# CW521_BallisticGel_Main.net
KiCad netlist of a schematic drawn in Altium Designer
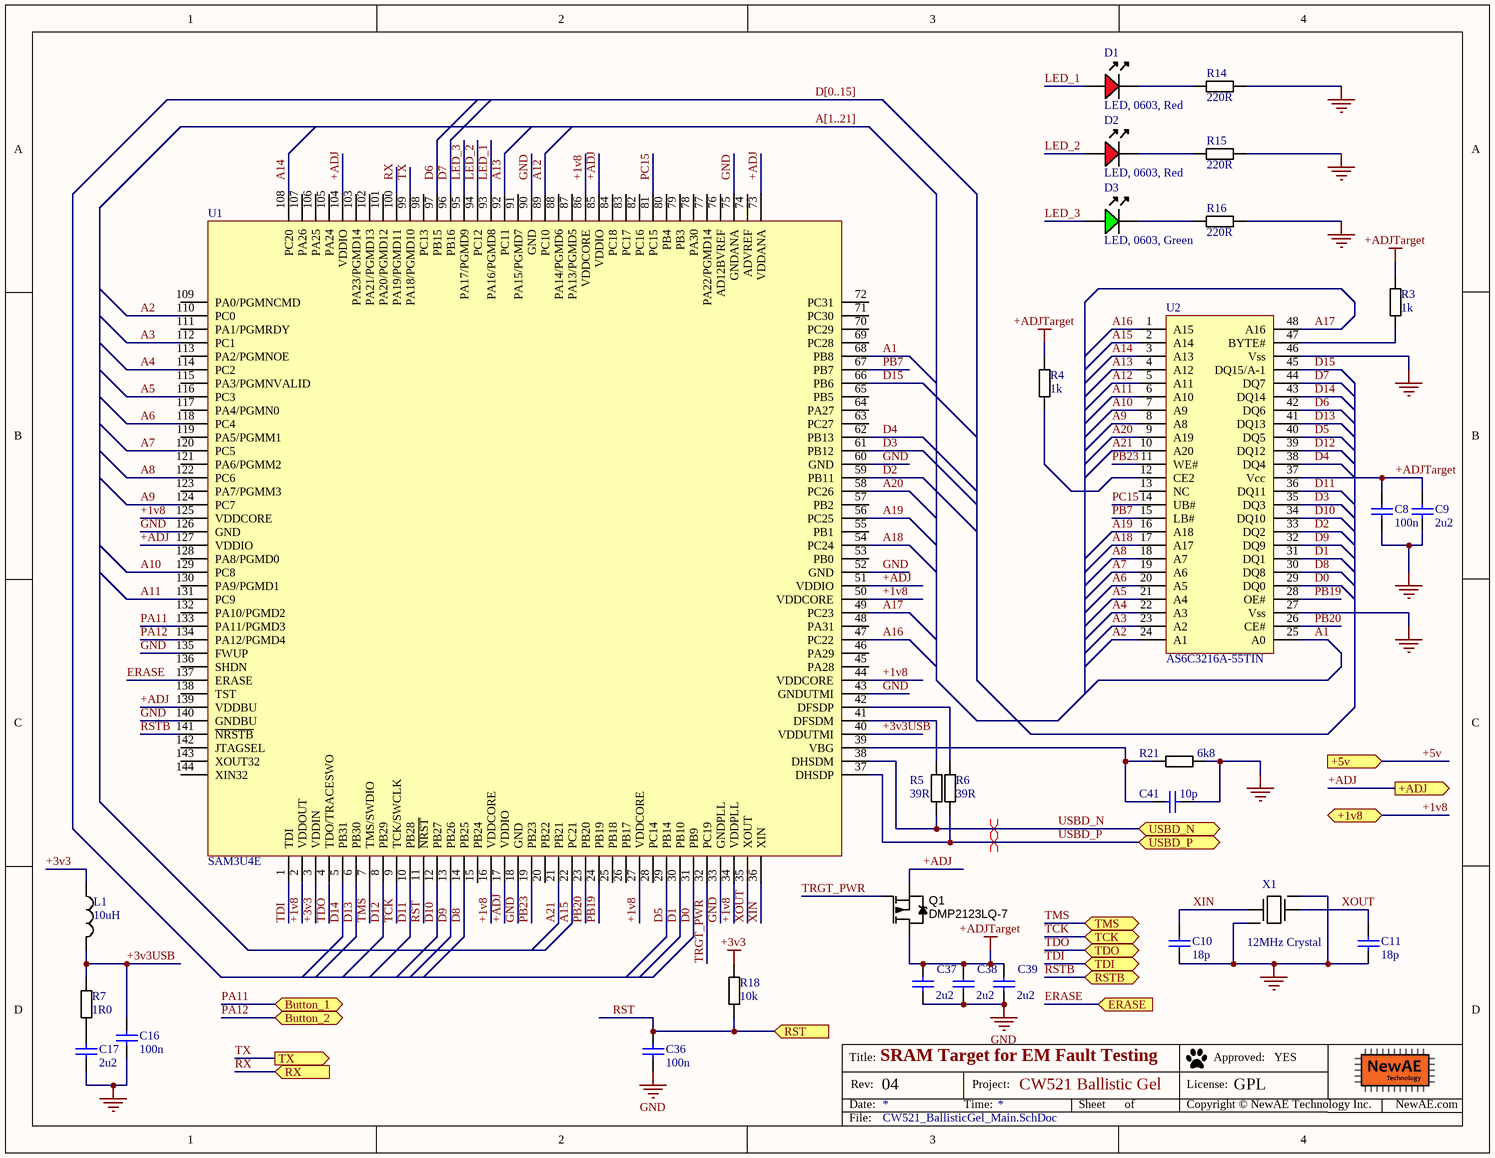
[diagram p0: CW521_BallisticGel_Main.SchDoc]

(export (version "E")
  (design (tool "Eeschema 10.0.6"))
  (components
    (comp (ref "C8")
      (value "100n")
      (footprint "CAPC0603_M")
      (description "100n, 0603")
      (fields (field (name "PART NUMBER") "CCHIP-100n-0603"))
      (libsource (lib "NewAE_AltiumLib") (part "CAP"))
    )
    (comp (ref "C9")
      (value "2u2")
      (footprint "CAPC0603_M")
      (description "2u2, 0603")
      (fields (field (name "PART NUMBER") "CCHIP-2u2-0603"))
      (libsource (lib "NewAE_AltiumLib") (part "CAP"))
    )
    (comp (ref "C10")
      (value "18p")
      (footprint "CAPC0402_M")
      (description "18p, 0402")
      (fields (field (name "PART NUMBER") "CCHIP-18p-0402"))
      (libsource (lib "NewAE_AltiumLib") (part "CAP"))
    )
    (comp (ref "C11")
      (value "18p")
      (footprint "CAPC0402_M")
      (description "18p, 0402")
      (fields (field (name "PART NUMBER") "CCHIP-18p-0402"))
      (libsource (lib "NewAE_AltiumLib") (part "CAP"))
    )
    (comp (ref "C16")
      (value "100n")
      (footprint "CAPC0603_M")
      (description "100n, 0603")
      (fields (field (name "PART NUMBER") "CCHIP-100n-0603"))
      (libsource (lib "NewAE_AltiumLib") (part "CAP"))
    )
    (comp (ref "C17")
      (value "2u2")
      (footprint "CAPC0603_M")
      (description "2u2, 0603")
      (fields (field (name "PART NUMBER") "CCHIP-2u2-0603"))
      (libsource (lib "NewAE_AltiumLib") (part "CAP"))
    )
    (comp (ref "C36")
      (value "100n")
      (footprint "CAPC0603_M")
      (description "100n, 0603")
      (fields (field (name "PART NUMBER") "CCHIP-100n-0603"))
      (libsource (lib "NewAE_AltiumLib") (part "CAP"))
    )
    (comp (ref "C37")
      (value "2u2")
      (footprint "CAPC0603_M")
      (description "2u2, 0603")
      (fields (field (name "PART NUMBER") "CCHIP-2u2-0603"))
      (libsource (lib "NewAE_AltiumLib") (part "CAP"))
    )
    (comp (ref "C38")
      (value "2u2")
      (footprint "CAPC0603_M")
      (description "2u2, 0603")
      (fields (field (name "PART NUMBER") "CCHIP-2u2-0603"))
      (libsource (lib "NewAE_AltiumLib") (part "CAP"))
    )
    (comp (ref "C39")
      (value "2u2")
      (footprint "CAPC0603_M")
      (description "2u2, 0603")
      (fields (field (name "PART NUMBER") "CCHIP-2u2-0603"))
      (libsource (lib "NewAE_AltiumLib") (part "CAP"))
    )
    (comp (ref "C41")
      (value "10p")
      (footprint "CAPC0603_M")
      (description "10p, 0603")
      (fields (field (name "PART NUMBER") "CCHIP-10p-0603"))
      (libsource (lib "NewAE_AltiumLib") (part "CAP"))
    )
    (comp (ref "D1")
      (value "LED, 0603, Red")
      (footprint "LED-0603-RED")
      (description "Chip LED, Red")
      (fields (field (name "PART NUMBER") "LEDCHIP_0603_RED"))
      (libsource (lib "NewAE_AltiumLib") (part "LED_RED"))
    )
    (comp (ref "D2")
      (value "LED, 0603, Red")
      (footprint "LED-0603-RED")
      (description "Chip LED, Red")
      (fields (field (name "PART NUMBER") "LEDCHIP_0603_RED"))
      (libsource (lib "NewAE_AltiumLib") (part "LED_RED"))
    )
    (comp (ref "D3")
      (value "LED, 0603, Green")
      (footprint "LED-0603-GREEN")
      (description "Chip LED, Green")
      (fields (field (name "PART NUMBER") "LEDCHIP_0603_GREEN"))
      (libsource (lib "NewAE_AltiumLib") (part "LED_GREEN"))
    )
    (comp (ref "L1")
      (value "10uH")
      (footprint "IND_0603")
      (description "FIXED IND 10UH 300MA 600 MOHM")
      (fields (field (name "PART NUMBER") "10uH_0603"))
      (libsource (lib "NewAE_AltiumLib") (part "IND"))
    )
    (comp (ref "Q1")
      (value "DMP2123LQ-7")
      (footprint "SOT95P245X110-3M")
      (description "P-Channel, 3A, Logic Level")
      (libsource (lib "NewAE_AltiumLib") (part "MOSFET_P_GSD"))
    )
    (comp (ref "R3")
      (value "1k")
      (footprint "RESC1608X55N")
      (description "1k res, 0603, 1%, 1/10W")
      (fields (field (name "PART NUMBER") "RCHIP-1K-0603") (field (name "TOLERANCE") "1%"))
      (libsource (lib "NewAE_AltiumLib") (part "RES-EU"))
    )
    (comp (ref "R4")
      (value "1k")
      (footprint "RESC1608X55N")
      (description "1k res, 0603, 1%, 1/10W")
      (fields (field (name "PART NUMBER") "RCHIP-1K-0603") (field (name "TOLERANCE") "1%"))
      (libsource (lib "NewAE_AltiumLib") (part "RES-EU"))
    )
    (comp (ref "R5")
      (value "39R")
      (footprint "RESC1608X55N")
      (description "39R res, 0603, 1%, 1/10W")
      (fields (field (name "PART NUMBER") "RCHIP-39R-0603") (field (name "TOLERANCE") "1%"))
      (libsource (lib "NewAE_AltiumLib") (part "RES-EU"))
    )
    (comp (ref "R6")
      (value "39R")
      (footprint "RESC1608X55N")
      (description "39R res, 0603, 1%, 1/10W")
      (fields (field (name "PART NUMBER") "RCHIP-39R-0603") (field (name "TOLERANCE") "1%"))
      (libsource (lib "NewAE_AltiumLib") (part "RES-EU"))
    )
    (comp (ref "R7")
      (value "1R0")
      (footprint "RESC1608X55N")
      (description "1R0 res, 0603, 1%, 1/10W")
      (fields (field (name "PART NUMBER") "RCHIP-1R0-0603") (field (name "TOLERANCE") "1%"))
      (libsource (lib "NewAE_AltiumLib") (part "RES-EU"))
    )
    (comp (ref "R14")
      (value "220R")
      (footprint "RESC1608X55N")
      (description "220R res, 0603, 1%, 1/10W")
      (fields (field (name "PART NUMBER") "RCHIP-220R-0603") (field (name "TOLERANCE") "1%"))
      (libsource (lib "") (part "RES-EU_1"))
    )
    (comp (ref "R15")
      (value "220R")
      (footprint "RESC1608X55N")
      (description "220R res, 0603, 1%, 1/10W")
      (fields (field (name "PART NUMBER") "RCHIP-220R-0603") (field (name "TOLERANCE") "1%"))
      (libsource (lib "") (part "RES-EU_1"))
    )
    (comp (ref "R16")
      (value "220R")
      (footprint "RESC1608X55N")
      (description "220R res, 0603, 1%, 1/10W")
      (fields (field (name "PART NUMBER") "RCHIP-220R-0603") (field (name "TOLERANCE") "1%"))
      (libsource (lib "") (part "RES-EU_1"))
    )
    (comp (ref "R18")
      (value "10k")
      (footprint "RESC1608X55N")
      (description "10k res, 0603, 1%, 1/10W")
      (fields (field (name "PART NUMBER") "RCHIP-10K-0603") (field (name "TOLERANCE") "1%"))
      (libsource (lib "NewAE_AltiumLib") (part "RES-EU"))
    )
    (comp (ref "R21")
      (value "6k8")
      (footprint "RESC1608X55N")
      (description "6k8 res, 0603, 1%, 1/10W")
      (fields (field (name "PART NUMBER") "RCHIP-6K8-0603") (field (name "TOLERANCE") "1%"))
      (libsource (lib "") (part "RES-EU_1"))
    )
    (comp (ref "U1")
      (value "SAM3U4E")
      (footprint "LQFP-144_0.5")
      (description "IC MCU 32BIT 256KB FLASH 144LQFP")
      (libsource (lib "NewAE_AltiumLib") (part "SAM3U4E"))
    )
    (comp (ref "U2")
      (value "AS6C3216A-55TIN")
      (footprint "TSSOP-48_0.5")
      (description "IC SRAM 32MBIT 55NS 48TSSOP")
      (fields (field (name "PART NUMBER") "AS6C3216A"))
      (libsource (lib "NewAE_AltiumLib") (part "AS6C3216"))
    )
    (comp (ref "X1")
      (value "12MHz Crystal")
      (footprint "ABM8G")
      (description "CRYSTAL 12.0000MHZ 10PF SMD")
      (fields (field (name "PART NUMBER") "ABM8G"))
      (libsource (lib "NewAE_AltiumLib") (part "OSC_4pin"))
    )
  )
  (nets
    (net (code "1") (name "+3v3") (class "Default")
      (node (ref "L1") (pin "1") (pinfunction "1_1") (pintype "passive"))
      (node (ref "R18") (pin "1") (pinfunction "1_1") (pintype "passive"))
      (node (ref "U1") (pin "3") (pinfunction "VDDIN_3") (pintype "passive"))
    )
    (net (code "2") (name "+ADJTarget") (class "Default")
      (node (ref "C37") (pin "1") (pinfunction "1_1") (pintype "passive"))
      (node (ref "C38") (pin "1") (pinfunction "1_1") (pintype "passive"))
      (node (ref "C39") (pin "1") (pinfunction "1_1") (pintype "passive"))
      (node (ref "C8") (pin "1") (pinfunction "1_1") (pintype "passive"))
      (node (ref "C9") (pin "1") (pinfunction "1_1") (pintype "passive"))
      (node (ref "Q1") (pin "3") (pinfunction "D_3") (pintype "passive"))
      (node (ref "R3") (pin "1") (pinfunction "1_1") (pintype "passive"))
      (node (ref "R4") (pin "1") (pinfunction "1_1") (pintype "passive"))
      (node (ref "U2") (pin "37") (pinfunction "Vcc_37") (pintype "passive"))
    )
    (net (code "3") (name "/+1v8") (class "Default")
      (node (ref "U1") (pin "125") (pinfunction "VDDCORE_125") (pintype "passive"))
      (node (ref "U1") (pin "16") (pinfunction "VDDCORE_16") (pintype "passive"))
      (node (ref "U1") (pin "2") (pinfunction "VDDOUT_2") (pintype "passive"))
      (node (ref "U1") (pin "27") (pinfunction "VDDCORE_27") (pintype "passive"))
      (node (ref "U1") (pin "34") (pinfunction "VDDPLL_34") (pintype "passive"))
      (node (ref "U1") (pin "44") (pinfunction "VDDCORE_44") (pintype "passive"))
      (node (ref "U1") (pin "50") (pinfunction "VDDCORE_50") (pintype "passive"))
      (node (ref "U1") (pin "86") (pinfunction "VDDCORE_86") (pintype "passive"))
    )
    (net (code "4") (name "/+3v3USB") (class "Default")
      (node (ref "C16") (pin "1") (pinfunction "1_1") (pintype "passive"))
      (node (ref "L1") (pin "2") (pinfunction "2_2") (pintype "passive"))
      (node (ref "R7") (pin "1") (pinfunction "1_1") (pintype "passive"))
      (node (ref "U1") (pin "40") (pinfunction "VDDUTMI_40") (pintype "passive"))
    )
    (net (code "6") (name "/+ADJ") (class "Default")
      (node (ref "Q1") (pin "2") (pinfunction "S_2") (pintype "passive"))
      (node (ref "U1") (pin "104") (pinfunction "VDDIO_104") (pintype "passive"))
      (node (ref "U1") (pin "127") (pinfunction "VDDIO_127") (pintype "passive"))
      (node (ref "U1") (pin "139") (pinfunction "VDDBU_139") (pintype "passive"))
      (node (ref "U1") (pin "17") (pinfunction "VDDIO_17") (pintype "passive"))
      (node (ref "U1") (pin "51") (pinfunction "VDDIO_51") (pintype "passive"))
      (node (ref "U1") (pin "73") (pinfunction "VDDANA_73") (pintype "passive"))
      (node (ref "U1") (pin "85") (pinfunction "VDDIO_85") (pintype "passive"))
    )
    (net (code "7") (name "/A1") (class "Default")
      (node (ref "U1") (pin "68") (pinfunction "PB8_68") (pintype "passive"))
      (node (ref "U2") (pin "25") (pinfunction "A0_25") (pintype "passive"))
    )
    (net (code "8") (name "/A2") (class "Default")
      (node (ref "U1") (pin "110") (pinfunction "PC0_110") (pintype "passive"))
      (node (ref "U2") (pin "24") (pinfunction "A1_24") (pintype "passive"))
    )
    (net (code "9") (name "/A3") (class "Default")
      (node (ref "U1") (pin "112") (pinfunction "PC1_112") (pintype "passive"))
      (node (ref "U2") (pin "23") (pinfunction "A2_23") (pintype "passive"))
    )
    (net (code "10") (name "/A4") (class "Default")
      (node (ref "U1") (pin "114") (pinfunction "PC2_114") (pintype "passive"))
      (node (ref "U2") (pin "22") (pinfunction "A3_22") (pintype "passive"))
    )
    (net (code "11") (name "/A5") (class "Default")
      (node (ref "U1") (pin "116") (pinfunction "PC3_116") (pintype "passive"))
      (node (ref "U2") (pin "21") (pinfunction "A4_21") (pintype "passive"))
    )
    (net (code "12") (name "/A6") (class "Default")
      (node (ref "U1") (pin "118") (pinfunction "PC4_118") (pintype "passive"))
      (node (ref "U2") (pin "20") (pinfunction "A5_20") (pintype "passive"))
    )
    (net (code "13") (name "/A7") (class "Default")
      (node (ref "U1") (pin "120") (pinfunction "PC5_120") (pintype "passive"))
      (node (ref "U2") (pin "19") (pinfunction "A6_19") (pintype "passive"))
    )
    (net (code "14") (name "/A8") (class "Default")
      (node (ref "U1") (pin "122") (pinfunction "PC6_122") (pintype "passive"))
      (node (ref "U2") (pin "18") (pinfunction "A7_18") (pintype "passive"))
    )
    (net (code "15") (name "/A9") (class "Default")
      (node (ref "U1") (pin "124") (pinfunction "PC7_124") (pintype "passive"))
      (node (ref "U2") (pin "8") (pinfunction "A8_8") (pintype "passive"))
    )
    (net (code "16") (name "/A10") (class "Default")
      (node (ref "U1") (pin "129") (pinfunction "PC8_129") (pintype "passive"))
      (node (ref "U2") (pin "7") (pinfunction "A9_7") (pintype "passive"))
    )
    (net (code "17") (name "/A11") (class "Default")
      (node (ref "U1") (pin "131") (pinfunction "PC9_131") (pintype "passive"))
      (node (ref "U2") (pin "6") (pinfunction "A10_6") (pintype "passive"))
    )
    (net (code "18") (name "/A12") (class "Default")
      (node (ref "U1") (pin "89") (pinfunction "PC10_89") (pintype "passive"))
      (node (ref "U2") (pin "5") (pinfunction "A11_5") (pintype "passive"))
    )
    (net (code "19") (name "/A13") (class "Default")
      (node (ref "U1") (pin "92") (pinfunction "PC11_92") (pintype "passive"))
      (node (ref "U2") (pin "4") (pinfunction "A12_4") (pintype "passive"))
    )
    (net (code "20") (name "/A14") (class "Default")
      (node (ref "U1") (pin "108") (pinfunction "PC20_108") (pintype "passive"))
      (node (ref "U2") (pin "3") (pinfunction "A13_3") (pintype "passive"))
    )
    (net (code "21") (name "/A15") (class "Default")
      (node (ref "U1") (pin "22") (pinfunction "PC21_22") (pintype "passive"))
      (node (ref "U2") (pin "2") (pinfunction "A14_2") (pintype "passive"))
    )
    (net (code "22") (name "/A16") (class "Default")
      (node (ref "U1") (pin "47") (pinfunction "PC22_47") (pintype "passive"))
      (node (ref "U2") (pin "1") (pinfunction "A15_1") (pintype "passive"))
    )
    (net (code "23") (name "/A17") (class "Default")
      (node (ref "U1") (pin "49") (pinfunction "PC23_49") (pintype "passive"))
      (node (ref "U2") (pin "48") (pinfunction "A16_48") (pintype "passive"))
    )
    (net (code "24") (name "/A18") (class "Default")
      (node (ref "U1") (pin "54") (pinfunction "PC24_54") (pintype "passive"))
      (node (ref "U2") (pin "17") (pinfunction "A17_17") (pintype "passive"))
    )
    (net (code "25") (name "/A19") (class "Default")
      (node (ref "U1") (pin "56") (pinfunction "PC25_56") (pintype "passive"))
      (node (ref "U2") (pin "16") (pinfunction "A18_16") (pintype "passive"))
    )
    (net (code "26") (name "/A20") (class "Default")
      (node (ref "U1") (pin "58") (pinfunction "PC26_58") (pintype "passive"))
      (node (ref "U2") (pin "9") (pinfunction "A19_9") (pintype "passive"))
    )
    (net (code "27") (name "/A21") (class "Default")
      (node (ref "U1") (pin "21") (pinfunction "PB21_21") (pintype "passive"))
      (node (ref "U2") (pin "10") (pinfunction "A20_10") (pintype "passive"))
    )
    (net (code "29") (name "/D0") (class "Default")
      (node (ref "U1") (pin "31") (pinfunction "PB9_31") (pintype "passive"))
      (node (ref "U2") (pin "29") (pinfunction "DQ0_29") (pintype "passive"))
    )
    (net (code "30") (name "/D1") (class "Default")
      (node (ref "U1") (pin "30") (pinfunction "PB10_30") (pintype "passive"))
      (node (ref "U2") (pin "31") (pinfunction "DQ1_31") (pintype "passive"))
    )
    (net (code "31") (name "/D2") (class "Default")
      (node (ref "U1") (pin "59") (pinfunction "PB11_59") (pintype "passive"))
      (node (ref "U2") (pin "33") (pinfunction "DQ2_33") (pintype "passive"))
    )
    (net (code "32") (name "/D3") (class "Default")
      (node (ref "U1") (pin "61") (pinfunction "PB12_61") (pintype "passive"))
      (node (ref "U2") (pin "35") (pinfunction "DQ3_35") (pintype "passive"))
    )
    (net (code "33") (name "/D4") (class "Default")
      (node (ref "U1") (pin "62") (pinfunction "PB13_62") (pintype "passive"))
      (node (ref "U2") (pin "38") (pinfunction "DQ4_38") (pintype "passive"))
    )
    (net (code "34") (name "/D5") (class "Default")
      (node (ref "U1") (pin "29") (pinfunction "PB14_29") (pintype "passive"))
      (node (ref "U2") (pin "40") (pinfunction "DQ5_40") (pintype "passive"))
    )
    (net (code "35") (name "/D6") (class "Default")
      (node (ref "U1") (pin "97") (pinfunction "PB15_97") (pintype "passive"))
      (node (ref "U2") (pin "42") (pinfunction "DQ6_42") (pintype "passive"))
    )
    (net (code "36") (name "/D7") (class "Default")
      (node (ref "U1") (pin "96") (pinfunction "PB16_96") (pintype "passive"))
      (node (ref "U2") (pin "44") (pinfunction "DQ7_44") (pintype "passive"))
    )
    (net (code "37") (name "/D8") (class "Default")
      (node (ref "U1") (pin "14") (pinfunction "PB25_14") (pintype "passive"))
      (node (ref "U2") (pin "30") (pinfunction "DQ8_30") (pintype "passive"))
    )
    (net (code "38") (name "/D9") (class "Default")
      (node (ref "U1") (pin "13") (pinfunction "PB26_13") (pintype "passive"))
      (node (ref "U2") (pin "32") (pinfunction "DQ9_32") (pintype "passive"))
    )
    (net (code "39") (name "/D10") (class "Default")
      (node (ref "U1") (pin "12") (pinfunction "PB27_12") (pintype "passive"))
      (node (ref "U2") (pin "34") (pinfunction "DQ10_34") (pintype "passive"))
    )
    (net (code "40") (name "/D11") (class "Default")
      (node (ref "U1") (pin "10") (pinfunction "PB28_10") (pintype "passive"))
      (node (ref "U2") (pin "36") (pinfunction "DQ11_36") (pintype "passive"))
    )
    (net (code "41") (name "/D12") (class "Default")
      (node (ref "U1") (pin "8") (pinfunction "PB29_8") (pintype "passive"))
      (node (ref "U2") (pin "39") (pinfunction "DQ12_39") (pintype "passive"))
    )
    (net (code "42") (name "/D13") (class "Default")
      (node (ref "U1") (pin "6") (pinfunction "PB30_6") (pintype "passive"))
      (node (ref "U2") (pin "41") (pinfunction "DQ13_41") (pintype "passive"))
    )
    (net (code "43") (name "/D14") (class "Default")
      (node (ref "U1") (pin "5") (pinfunction "PB31_5") (pintype "passive"))
      (node (ref "U2") (pin "43") (pinfunction "DQ14_43") (pintype "passive"))
    )
    (net (code "44") (name "/D15") (class "Default")
      (node (ref "U1") (pin "66") (pinfunction "PB6_66") (pintype "passive"))
      (node (ref "U2") (pin "45") (pinfunction "DQ15/A-1_45") (pintype "passive"))
    )
    (net (code "46") (name "/ERASE") (class "Default")
      (node (ref "U1") (pin "137") (pinfunction "ERASE_137") (pintype "passive"))
    )
    (net (code "47") (name "/LED_1") (class "Default")
      (node (ref "D1") (pin "A") (pinfunction "A_A") (pintype "passive"))
      (node (ref "U1") (pin "93") (pinfunction "PA16/PGMD8_93") (pintype "passive"))
    )
    (net (code "48") (name "/LED_2") (class "Default")
      (node (ref "D2") (pin "A") (pinfunction "A_A") (pintype "passive"))
      (node (ref "U1") (pin "94") (pinfunction "PC12_94") (pintype "passive"))
    )
    (net (code "49") (name "/LED_3") (class "Default")
      (node (ref "D3") (pin "A") (pinfunction "A_A") (pintype "passive"))
      (node (ref "U1") (pin "95") (pinfunction "PA17/PGMD9_95") (pintype "passive"))
    )
    (net (code "50") (name "/PA11") (class "Default")
      (node (ref "U1") (pin "133") (pinfunction "PA11/PGMD3_133") (pintype "passive"))
    )
    (net (code "51") (name "/PA12") (class "Default")
      (node (ref "U1") (pin "134") (pinfunction "PA12/PGMD4_134") (pintype "passive"))
    )
    (net (code "52") (name "/PB7") (class "Default")
      (node (ref "U1") (pin "67") (pinfunction "PB7_67") (pintype "passive"))
      (node (ref "U2") (pin "15") (pinfunction "LB#_15") (pintype "passive"))
    )
    (net (code "53") (name "/PB19") (class "Default")
      (node (ref "U1") (pin "24") (pinfunction "PB19_24") (pintype "passive"))
      (node (ref "U2") (pin "28") (pinfunction "OE#_28") (pintype "passive"))
    )
    (net (code "54") (name "/PB20") (class "Default")
      (node (ref "U1") (pin "23") (pinfunction "PB20_23") (pintype "passive"))
      (node (ref "U2") (pin "26") (pinfunction "CE#_26") (pintype "passive"))
    )
    (net (code "55") (name "/PB23") (class "Default")
      (node (ref "U1") (pin "19") (pinfunction "PB23_19") (pintype "passive"))
      (node (ref "U2") (pin "11") (pinfunction "WE#_11") (pintype "passive"))
    )
    (net (code "56") (name "/PC15") (class "Default")
      (node (ref "U1") (pin "81") (pinfunction "PC15_81") (pintype "passive"))
      (node (ref "U2") (pin "14") (pinfunction "UB#_14") (pintype "passive"))
    )
    (net (code "57") (name "/RST") (class "Default")
      (node (ref "C36") (pin "1") (pinfunction "1_1") (pintype "passive"))
      (node (ref "R18") (pin "2") (pinfunction "2_2") (pintype "passive"))
      (node (ref "U1") (pin "11") (pinfunction "~{NRST}_11") (pintype "passive"))
    )
    (net (code "58") (name "/RSTB") (class "Default")
      (node (ref "U1") (pin "141") (pinfunction "~{NRSTB}_141") (pintype "passive"))
    )
    (net (code "59") (name "/RX") (class "Default")
      (node (ref "U1") (pin "100") (pinfunction "PA19/PGMD11_100") (pintype "passive"))
    )
    (net (code "60") (name "/TCK") (class "Default")
      (node (ref "U1") (pin "9") (pinfunction "TCK/SWCLK_9") (pintype "passive"))
    )
    (net (code "61") (name "/TDI") (class "Default")
      (node (ref "U1") (pin "1") (pinfunction "TDI_1") (pintype "passive"))
    )
    (net (code "62") (name "/TDO") (class "Default")
      (node (ref "U1") (pin "4") (pinfunction "TDO/TRACESWO_4") (pintype "passive"))
    )
    (net (code "63") (name "/TMS") (class "Default")
      (node (ref "U1") (pin "7") (pinfunction "TMS/SWDIO_7") (pintype "passive"))
    )
    (net (code "64") (name "/TRGT_PWR") (class "Default")
      (node (ref "Q1") (pin "1") (pinfunction "G_1") (pintype "passive"))
      (node (ref "U1") (pin "32") (pinfunction "PC19_32") (pintype "passive"))
    )
    (net (code "65") (name "/TX") (class "Default")
      (node (ref "U1") (pin "99") (pinfunction "PA18/PGMD10_99") (pintype "passive"))
    )
    (net (code "66") (name "/USBD_N") (class "Default")
      (node (ref "R5") (pin "2") (pinfunction "2_2") (pintype "passive"))
      (node (ref "U1") (pin "38") (pinfunction "DHSDM_38") (pintype "passive"))
    )
    (net (code "67") (name "/USBD_P") (class "Default")
      (node (ref "R6") (pin "2") (pinfunction "2_2") (pintype "passive"))
      (node (ref "U1") (pin "37") (pinfunction "DHSDP_37") (pintype "passive"))
    )
    (net (code "68") (name "/XIN") (class "Default")
      (node (ref "C10") (pin "1") (pinfunction "1_1") (pintype "passive"))
      (node (ref "U1") (pin "36") (pinfunction "XIN_36") (pintype "passive"))
      (node (ref "X1") (pin "1") (pinfunction "1_1") (pintype "passive"))
    )
    (net (code "69") (name "/XOUT") (class "Default")
      (node (ref "C11") (pin "1") (pinfunction "1_1") (pintype "passive"))
      (node (ref "U1") (pin "35") (pinfunction "XOUT_35") (pintype "passive"))
      (node (ref "X1") (pin "3") (pinfunction "3_3") (pintype "passive"))
    )
    (net (code "70") (name "GND") (class "Default")
      (node (ref "C10") (pin "2") (pinfunction "2_2") (pintype "passive"))
      (node (ref "C11") (pin "2") (pinfunction "2_2") (pintype "passive"))
      (node (ref "C16") (pin "2") (pinfunction "2_2") (pintype "passive"))
      (node (ref "C17") (pin "2") (pinfunction "2_2") (pintype "passive"))
      (node (ref "C36") (pin "2") (pinfunction "2_2") (pintype "passive"))
      (node (ref "C37") (pin "2") (pinfunction "2_2") (pintype "passive"))
      (node (ref "C38") (pin "2") (pinfunction "2_2") (pintype "passive"))
      (node (ref "C39") (pin "2") (pinfunction "2_2") (pintype "passive"))
      (node (ref "C41") (pin "2") (pinfunction "2_2") (pintype "passive"))
      (node (ref "C8") (pin "2") (pinfunction "2_2") (pintype "passive"))
      (node (ref "C9") (pin "2") (pinfunction "2_2") (pintype "passive"))
      (node (ref "R14") (pin "2") (pinfunction "2_2") (pintype "passive"))
      (node (ref "R15") (pin "2") (pinfunction "2_2") (pintype "passive"))
      (node (ref "R16") (pin "2") (pinfunction "2_2") (pintype "passive"))
      (node (ref "R21") (pin "2") (pinfunction "2_2") (pintype "passive"))
      (node (ref "U1") (pin "126") (pinfunction "GND_126") (pintype "passive"))
      (node (ref "U1") (pin "135") (pinfunction "FWUP_135") (pintype "passive"))
      (node (ref "U1") (pin "140") (pinfunction "GNDBU_140") (pintype "passive"))
      (node (ref "U1") (pin "18") (pinfunction "GND_18") (pintype "passive"))
      (node (ref "U1") (pin "33") (pinfunction "GNDPLL_33") (pintype "passive"))
      (node (ref "U1") (pin "43") (pinfunction "GNDUTMI_43") (pintype "passive"))
      (node (ref "U1") (pin "52") (pinfunction "GND_52") (pintype "passive"))
      (node (ref "U1") (pin "60") (pinfunction "GND_60") (pintype "passive"))
      (node (ref "U1") (pin "75") (pinfunction "GNDANA_75") (pintype "passive"))
      (node (ref "U1") (pin "90") (pinfunction "GND_90") (pintype "passive"))
      (node (ref "U2") (pin "27") (pinfunction "Vss_27") (pintype "passive"))
      (node (ref "U2") (pin "46") (pinfunction "Vss_46") (pintype "passive"))
      (node (ref "X1") (pin "2") (pinfunction "2_2") (pintype "passive"))
      (node (ref "X1") (pin "4") (pinfunction "4_4") (pintype "passive"))
    )
    (net (code "71") (name "Net-(C17-Pad1)") (class "Default")
      (node (ref "C17") (pin "1") (pinfunction "1_1") (pintype "passive"))
      (node (ref "R7") (pin "2") (pinfunction "2_2") (pintype "passive"))
    )
    (net (code "72") (name "Net-(D1-PadK)") (class "Default")
      (node (ref "D1") (pin "K") (pinfunction "K_K") (pintype "passive"))
      (node (ref "R14") (pin "1") (pinfunction "1_1") (pintype "passive"))
    )
    (net (code "73") (name "Net-(D2-PadK)") (class "Default")
      (node (ref "D2") (pin "K") (pinfunction "K_K") (pintype "passive"))
      (node (ref "R15") (pin "1") (pinfunction "1_1") (pintype "passive"))
    )
    (net (code "74") (name "Net-(D3-PadK)") (class "Default")
      (node (ref "D3") (pin "K") (pinfunction "K_K") (pintype "passive"))
      (node (ref "R16") (pin "1") (pinfunction "1_1") (pintype "passive"))
    )
    (net (code "75") (name "Net-(U1-DFSDM)") (class "Default")
      (node (ref "R5") (pin "1") (pinfunction "1_1") (pintype "passive"))
      (node (ref "U1") (pin "41") (pinfunction "DFSDM_41") (pintype "passive"))
    )
    (net (code "76") (name "Net-(U1-DFSDP)") (class "Default")
      (node (ref "R6") (pin "1") (pinfunction "1_1") (pintype "passive"))
      (node (ref "U1") (pin "42") (pinfunction "DFSDP_42") (pintype "passive"))
    )
    (net (code "77") (name "Net-(U1-VBG)") (class "Default")
      (node (ref "C41") (pin "1") (pinfunction "1_1") (pintype "passive"))
      (node (ref "R21") (pin "1") (pinfunction "1_1") (pintype "passive"))
      (node (ref "U1") (pin "39") (pinfunction "VBG_39") (pintype "passive"))
    )
    (net (code "78") (name "Net-(U2-BYTE#)") (class "Default")
      (node (ref "R3") (pin "2") (pinfunction "2_2") (pintype "passive"))
      (node (ref "U2") (pin "47") (pinfunction "BYTE#_47") (pintype "passive"))
    )
    (net (code "79") (name "Net-(U2-CE2)") (class "Default")
      (node (ref "R4") (pin "2") (pinfunction "2_2") (pintype "passive"))
      (node (ref "U2") (pin "12") (pinfunction "CE2_12") (pintype "passive"))
    )
    (net (code "80") (name "unconnected-(U1-AD12BVREF-Pad76)") (class "Default")
      (node (ref "U1") (pin "76") (pinfunction "AD12BVREF_76") (pintype "passive"))
    )
    (net (code "81") (name "unconnected-(U1-ADVREF-Pad74)") (class "Default")
      (node (ref "U1") (pin "74") (pinfunction "ADVREF_74") (pintype "passive"))
    )
    (net (code "82") (name "unconnected-(U1-JTAGSEL-Pad142)") (class "Default")
      (node (ref "U1") (pin "142") (pinfunction "JTAGSEL_142") (pintype "passive"))
    )
    (net (code "83") (name "unconnected-(U1-PA0{slash}PGMNCMD-Pad109)") (class "Default")
      (node (ref "U1") (pin "109") (pinfunction "PA0/PGMNCMD_109") (pintype "passive"))
    )
    (net (code "84") (name "unconnected-(U1-PA1{slash}PGMRDY-Pad111)") (class "Default")
      (node (ref "U1") (pin "111") (pinfunction "PA1/PGMRDY_111") (pintype "passive"))
    )
    (net (code "85") (name "unconnected-(U1-PA2{slash}PGMNOE-Pad113)") (class "Default")
      (node (ref "U1") (pin "113") (pinfunction "PA2/PGMNOE_113") (pintype "passive"))
    )
    (net (code "86") (name "unconnected-(U1-PA3{slash}PGMNVALID-Pad115)") (class "Default")
      (node (ref "U1") (pin "115") (pinfunction "PA3/PGMNVALID_115") (pintype "passive"))
    )
    (net (code "87") (name "unconnected-(U1-PA4{slash}PGMN0-Pad117)") (class "Default")
      (node (ref "U1") (pin "117") (pinfunction "PA4/PGMN0_117") (pintype "passive"))
    )
    (net (code "88") (name "unconnected-(U1-PA5{slash}PGMM1-Pad119)") (class "Default")
      (node (ref "U1") (pin "119") (pinfunction "PA5/PGMM1_119") (pintype "passive"))
    )
    (net (code "89") (name "unconnected-(U1-PA6{slash}PGMM2-Pad121)") (class "Default")
      (node (ref "U1") (pin "121") (pinfunction "PA6/PGMM2_121") (pintype "passive"))
    )
    (net (code "90") (name "unconnected-(U1-PA7{slash}PGMM3-Pad123)") (class "Default")
      (node (ref "U1") (pin "123") (pinfunction "PA7/PGMM3_123") (pintype "passive"))
    )
    (net (code "91") (name "unconnected-(U1-PA8{slash}PGMD0-Pad128)") (class "Default")
      (node (ref "U1") (pin "128") (pinfunction "PA8/PGMD0_128") (pintype "passive"))
    )
    (net (code "92") (name "unconnected-(U1-PA9{slash}PGMD1-Pad130)") (class "Default")
      (node (ref "U1") (pin "130") (pinfunction "PA9/PGMD1_130") (pintype "passive"))
    )
    (net (code "93") (name "unconnected-(U1-PA10{slash}PGMD2-Pad132)") (class "Default")
      (node (ref "U1") (pin "132") (pinfunction "PA10/PGMD2_132") (pintype "passive"))
    )
    (net (code "94") (name "unconnected-(U1-PA13{slash}PGMD5-Pad87)") (class "Default")
      (node (ref "U1") (pin "87") (pinfunction "PA13/PGMD5_87") (pintype "passive"))
    )
    (net (code "95") (name "unconnected-(U1-PA14{slash}PGMD6-Pad88)") (class "Default")
      (node (ref "U1") (pin "88") (pinfunction "PA14/PGMD6_88") (pintype "passive"))
    )
    (net (code "96") (name "unconnected-(U1-PA15{slash}PGMD7-Pad91)") (class "Default")
      (node (ref "U1") (pin "91") (pinfunction "PA15/PGMD7_91") (pintype "passive"))
    )
    (net (code "97") (name "unconnected-(U1-PA20{slash}PGMD12-Pad101)") (class "Default")
      (node (ref "U1") (pin "101") (pinfunction "PA20/PGMD12_101") (pintype "passive"))
    )
    (net (code "98") (name "unconnected-(U1-PA21{slash}PGMD13-Pad102)") (class "Default")
      (node (ref "U1") (pin "102") (pinfunction "PA21/PGMD13_102") (pintype "passive"))
    )
    (net (code "99") (name "unconnected-(U1-PA22{slash}PGMD14-Pad77)") (class "Default")
      (node (ref "U1") (pin "77") (pinfunction "PA22/PGMD14_77") (pintype "passive"))
    )
    (net (code "100") (name "unconnected-(U1-PA23{slash}PGMD14-Pad103)") (class "Default")
      (node (ref "U1") (pin "103") (pinfunction "PA23/PGMD14_103") (pintype "passive"))
    )
    (net (code "101") (name "unconnected-(U1-PA24-Pad105)") (class "Default")
      (node (ref "U1") (pin "105") (pinfunction "PA24_105") (pintype "passive"))
    )
    (net (code "102") (name "unconnected-(U1-PA25-Pad106)") (class "Default")
      (node (ref "U1") (pin "106") (pinfunction "PA25_106") (pintype "passive"))
    )
    (net (code "103") (name "unconnected-(U1-PA26-Pad107)") (class "Default")
      (node (ref "U1") (pin "107") (pinfunction "PA26_107") (pintype "passive"))
    )
    (net (code "104") (name "unconnected-(U1-PA27-Pad64)") (class "Default")
      (node (ref "U1") (pin "64") (pinfunction "PA27_64") (pintype "passive"))
    )
    (net (code "105") (name "unconnected-(U1-PA28-Pad45)") (class "Default")
      (node (ref "U1") (pin "45") (pinfunction "PA28_45") (pintype "passive"))
    )
    (net (code "106") (name "unconnected-(U1-PA29-Pad46)") (class "Default")
      (node (ref "U1") (pin "46") (pinfunction "PA29_46") (pintype "passive"))
    )
    (net (code "107") (name "unconnected-(U1-PA30-Pad78)") (class "Default")
      (node (ref "U1") (pin "78") (pinfunction "PA30_78") (pintype "passive"))
    )
    (net (code "108") (name "unconnected-(U1-PA31-Pad48)") (class "Default")
      (node (ref "U1") (pin "48") (pinfunction "PA31_48") (pintype "passive"))
    )
    (net (code "109") (name "unconnected-(U1-PB0-Pad53)") (class "Default")
      (node (ref "U1") (pin "53") (pinfunction "PB0_53") (pintype "passive"))
    )
    (net (code "110") (name "unconnected-(U1-PB1-Pad55)") (class "Default")
      (node (ref "U1") (pin "55") (pinfunction "PB1_55") (pintype "passive"))
    )
    (net (code "111") (name "unconnected-(U1-PB2-Pad57)") (class "Default")
      (node (ref "U1") (pin "57") (pinfunction "PB2_57") (pintype "passive"))
    )
    (net (code "112") (name "unconnected-(U1-PB3-Pad79)") (class "Default")
      (node (ref "U1") (pin "79") (pinfunction "PB3_79") (pintype "passive"))
    )
    (net (code "113") (name "unconnected-(U1-PB4-Pad80)") (class "Default")
      (node (ref "U1") (pin "80") (pinfunction "PB4_80") (pintype "passive"))
    )
    (net (code "114") (name "unconnected-(U1-PB5-Pad65)") (class "Default")
      (node (ref "U1") (pin "65") (pinfunction "PB5_65") (pintype "passive"))
    )
    (net (code "115") (name "unconnected-(U1-PB17-Pad26)") (class "Default")
      (node (ref "U1") (pin "26") (pinfunction "PB17_26") (pintype "passive"))
    )
    (net (code "116") (name "unconnected-(U1-PB18-Pad25)") (class "Default")
      (node (ref "U1") (pin "25") (pinfunction "PB18_25") (pintype "passive"))
    )
    (net (code "117") (name "unconnected-(U1-PB22-Pad20)") (class "Default")
      (node (ref "U1") (pin "20") (pinfunction "PB22_20") (pintype "passive"))
    )
    (net (code "118") (name "unconnected-(U1-PB24-Pad15)") (class "Default")
      (node (ref "U1") (pin "15") (pinfunction "PB24_15") (pintype "passive"))
    )
    (net (code "119") (name "unconnected-(U1-PC13-Pad98)") (class "Default")
      (node (ref "U1") (pin "98") (pinfunction "PC13_98") (pintype "passive"))
    )
    (net (code "120") (name "unconnected-(U1-PC14-Pad28)") (class "Default")
      (node (ref "U1") (pin "28") (pinfunction "PC14_28") (pintype "passive"))
    )
    (net (code "121") (name "unconnected-(U1-PC16-Pad82)") (class "Default")
      (node (ref "U1") (pin "82") (pinfunction "PC16_82") (pintype "passive"))
    )
    (net (code "122") (name "unconnected-(U1-PC17-Pad83)") (class "Default")
      (node (ref "U1") (pin "83") (pinfunction "PC17_83") (pintype "passive"))
    )
    (net (code "123") (name "unconnected-(U1-PC18-Pad84)") (class "Default")
      (node (ref "U1") (pin "84") (pinfunction "PC18_84") (pintype "passive"))
    )
    (net (code "124") (name "unconnected-(U1-PC27-Pad63)") (class "Default")
      (node (ref "U1") (pin "63") (pinfunction "PC27_63") (pintype "passive"))
    )
    (net (code "125") (name "unconnected-(U1-PC28-Pad69)") (class "Default")
      (node (ref "U1") (pin "69") (pinfunction "PC28_69") (pintype "passive"))
    )
    (net (code "126") (name "unconnected-(U1-PC29-Pad70)") (class "Default")
      (node (ref "U1") (pin "70") (pinfunction "PC29_70") (pintype "passive"))
    )
    (net (code "127") (name "unconnected-(U1-PC30-Pad71)") (class "Default")
      (node (ref "U1") (pin "71") (pinfunction "PC30_71") (pintype "passive"))
    )
    (net (code "128") (name "unconnected-(U1-PC31-Pad72)") (class "Default")
      (node (ref "U1") (pin "72") (pinfunction "PC31_72") (pintype "passive"))
    )
    (net (code "129") (name "unconnected-(U1-SHDN-Pad136)") (class "Default")
      (node (ref "U1") (pin "136") (pinfunction "SHDN_136") (pintype "passive"))
    )
    (net (code "130") (name "unconnected-(U1-TST-Pad138)") (class "Default")
      (node (ref "U1") (pin "138") (pinfunction "TST_138") (pintype "passive"))
    )
    (net (code "131") (name "unconnected-(U1-XIN32-Pad144)") (class "Default")
      (node (ref "U1") (pin "144") (pinfunction "XIN32_144") (pintype "passive"))
    )
    (net (code "132") (name "unconnected-(U1-XOUT32-Pad143)") (class "Default")
      (node (ref "U1") (pin "143") (pinfunction "XOUT32_143") (pintype "passive"))
    )
    (net (code "133") (name "unconnected-(U2-NC-Pad13)") (class "Default")
      (node (ref "U2") (pin "13") (pinfunction "NC_13") (pintype "passive"))
    )
  )
)
